# sphericon_v2_lipo_safety.net
KiCad netlist of a schematic drawn in EAGLE
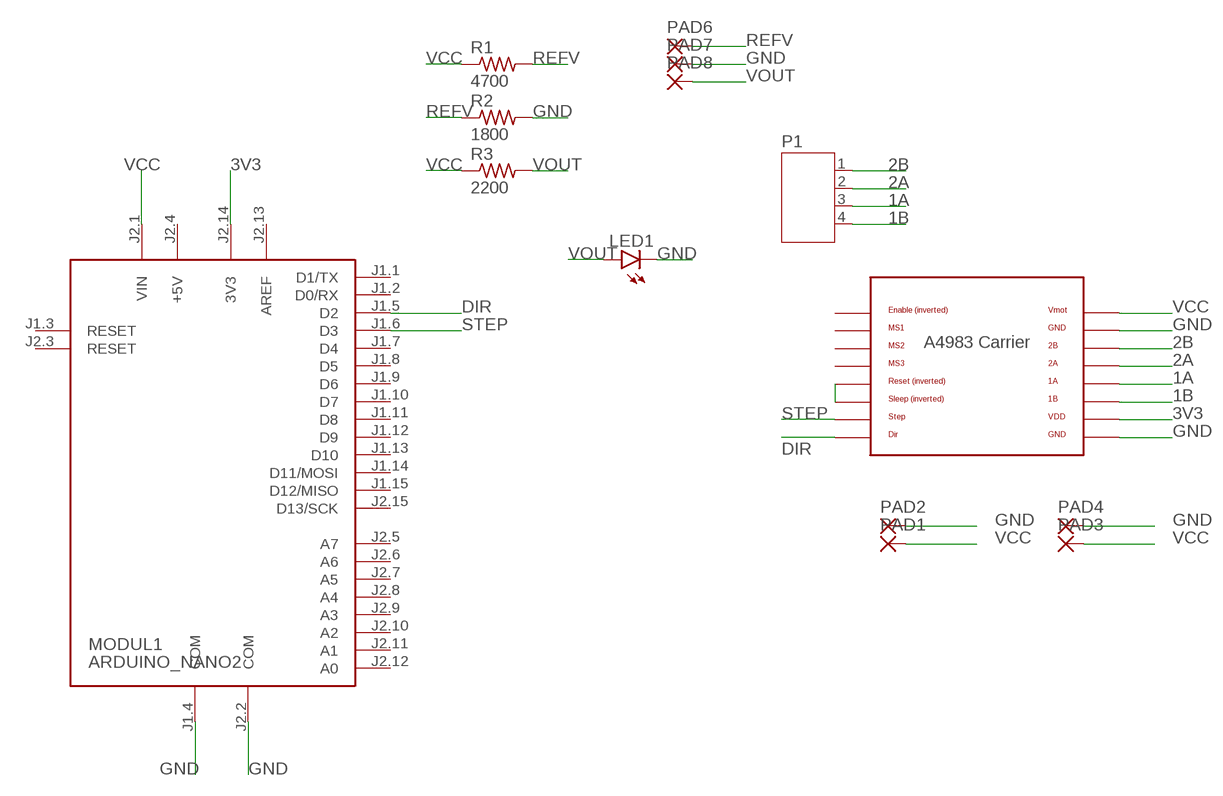
[diagram p0: schematic, sheet 1]

(export (version "E")
  (design (tool "Eeschema 10.0.6"))
  (components
    (comp (ref "LED1")
      (value "LED3MM")
      (footprint "eagle-import:LED3MM")
      (libsource (lib "eagle-import") (part "LED3MM"))
    )
    (comp (ref "MODUL1")
      (value "ARDUINO_NANO2")
      (footprint "eagle-import:ARDUINO_NANO2")
      (libsource (lib "eagle-import") (part "ARDUINO_NANO2"))
    )
    (comp (ref "P1")
      (value "JST-PH4")
      (footprint "eagle-import:JST-PH4")
      (libsource (lib "eagle-import") (part "JST-PH4"))
    )
    (comp (ref "PAD1")
      (value "1,6/0,8")
      (footprint "eagle-import:1,6_0,8")
      (libsource (lib "eagle-import") (part "1,6/0,8"))
    )
    (comp (ref "PAD2")
      (value "1,6/0,8")
      (footprint "eagle-import:1,6_0,8")
      (libsource (lib "eagle-import") (part "1,6/0,8"))
    )
    (comp (ref "PAD3")
      (value "1,6/0,8")
      (footprint "eagle-import:1,6_0,8")
      (libsource (lib "eagle-import") (part "1,6/0,8"))
    )
    (comp (ref "PAD4")
      (value "1,6/0,8")
      (footprint "eagle-import:1,6_0,8")
      (libsource (lib "eagle-import") (part "1,6/0,8"))
    )
    (comp (ref "PAD6")
      (value "1,6/0,8")
      (footprint "eagle-import:1,6_0,8")
      (libsource (lib "eagle-import") (part "1,6/0,8"))
    )
    (comp (ref "PAD7")
      (value "1,6/0,8")
      (footprint "eagle-import:1,6_0,8")
      (libsource (lib "eagle-import") (part "1,6/0,8"))
    )
    (comp (ref "PAD8")
      (value "1,6/0,8")
      (footprint "eagle-import:1,6_0,8")
      (libsource (lib "eagle-import") (part "1,6/0,8"))
    )
    (comp (ref "R1")
      (value "4700")
      (footprint "eagle-import:0204V")
      (libsource (lib "eagle-import") (part "R-US_0204/2V"))
    )
    (comp (ref "R2")
      (value "1800")
      (footprint "eagle-import:0204V")
      (libsource (lib "eagle-import") (part "R-US_0204/2V"))
    )
    (comp (ref "R3")
      (value "2200")
      (footprint "eagle-import:0204V")
      (libsource (lib "eagle-import") (part "R-US_0204/2V"))
    )
    (comp (ref "U$6")
      (value "POLOLU_A4983CARRIER")
      (footprint "eagle-import:A4983CARRIER")
      (libsource (lib "eagle-import") (part "POLOLU_A4983CARRIER"))
    )
  )
  (nets
    (net (code "1") (name "+5V") (class "Default")
      (node (ref "MODUL1") (pin "J2.4") (pinfunction "+5V_J2.4") (pintype "power_in"))
    )
    (net (code "2") (name "1A") (class "Default")
      (node (ref "P1") (pin "3") (pinfunction "3_3") (pintype "passive"))
      (node (ref "U$6") (pin "1A") (pinfunction "1A_1A") (pintype "output"))
    )
    (net (code "3") (name "1B") (class "Default")
      (node (ref "P1") (pin "4") (pinfunction "4_4") (pintype "passive"))
      (node (ref "U$6") (pin "1B") (pinfunction "1B_1B") (pintype "output"))
    )
    (net (code "4") (name "2A") (class "Default")
      (node (ref "P1") (pin "2") (pinfunction "2_2") (pintype "passive"))
      (node (ref "U$6") (pin "2A") (pinfunction "2A_2A") (pintype "output"))
    )
    (net (code "5") (name "2B") (class "Default")
      (node (ref "P1") (pin "1") (pinfunction "1_1") (pintype "passive"))
      (node (ref "U$6") (pin "2B") (pinfunction "2B_2B") (pintype "output"))
    )
    (net (code "6") (name "3V3") (class "Default")
      (node (ref "MODUL1") (pin "J2.14") (pinfunction "3V3_J2.14") (pintype "power_in"))
      (node (ref "U$6") (pin "VDD") (pinfunction "VDD_VDD") (pintype "power_in"))
    )
    (net (code "7") (name "AREF") (class "Default")
      (node (ref "MODUL1") (pin "J2.13") (pinfunction "AREF_J2.13") (pintype "power_in"))
    )
    (net (code "8") (name "DIR") (class "Default")
      (node (ref "MODUL1") (pin "J1.5") (pinfunction "D2_J1.5") (pintype "bidirectional"))
      (node (ref "U$6") (pin "DIR") (pinfunction "DIR_DIR") (pintype "input"))
    )
    (net (code "9") (name "GND") (class "Default")
      (node (ref "LED1") (pin "K") (pinfunction "C_K") (pintype "passive"))
      (node (ref "MODUL1") (pin "J1.4") (pinfunction "COM_J1.4") (pintype "power_in"))
      (node (ref "MODUL1") (pin "J2.2") (pinfunction "COM_J2.2") (pintype "power_in"))
      (node (ref "PAD2") (pin "1") (pinfunction "P_1") (pintype "passive"))
      (node (ref "PAD4") (pin "1") (pinfunction "P_1") (pintype "passive"))
      (node (ref "PAD7") (pin "1") (pinfunction "P_1") (pintype "passive"))
      (node (ref "R2") (pin "2") (pinfunction "2_2") (pintype "passive"))
      (node (ref "U$6") (pin "GND") (pinfunction "GND_GND") (pintype "power_in"))
      (node (ref "U$6") (pin "GND@0") (pinfunction "GND_GND@0") (pintype "power_in"))
    )
    (net (code "10") (name "Net-(U$6-SLEEP)") (class "Default")
      (node (ref "U$6") (pin "RST") (pinfunction "RST_RST") (pintype "input"))
      (node (ref "U$6") (pin "SLP") (pinfunction "SLEEP_SLP") (pintype "input"))
    )
    (net (code "11") (name "REFV") (class "Default")
      (node (ref "PAD6") (pin "1") (pinfunction "P_1") (pintype "passive"))
      (node (ref "R1") (pin "2") (pinfunction "2_2") (pintype "passive"))
      (node (ref "R2") (pin "1") (pinfunction "1_1") (pintype "passive"))
    )
    (net (code "12") (name "STEP") (class "Default")
      (node (ref "MODUL1") (pin "J1.6") (pinfunction "D3_J1.6") (pintype "bidirectional"))
      (node (ref "U$6") (pin "STEP") (pinfunction "STEP_STEP") (pintype "input"))
    )
    (net (code "13") (name "VCC") (class "Default")
      (node (ref "MODUL1") (pin "J2.1") (pinfunction "VIN_J2.1") (pintype "power_in"))
      (node (ref "PAD1") (pin "1") (pinfunction "P_1") (pintype "passive"))
      (node (ref "PAD3") (pin "1") (pinfunction "P_1") (pintype "passive"))
      (node (ref "R1") (pin "1") (pinfunction "1_1") (pintype "passive"))
      (node (ref "R3") (pin "1") (pinfunction "1_1") (pintype "passive"))
      (node (ref "U$6") (pin "VMOT") (pinfunction "VMOT_VMOT") (pintype "power_in"))
    )
    (net (code "14") (name "VOUT") (class "Default")
      (node (ref "LED1") (pin "A") (pinfunction "A_A") (pintype "passive"))
      (node (ref "PAD8") (pin "1") (pinfunction "P_1") (pintype "passive"))
      (node (ref "R3") (pin "2") (pinfunction "2_2") (pintype "passive"))
    )
    (net (code "15") (name "unconnected-(MODUL1-A0-PadJ2.12)") (class "Default")
      (node (ref "MODUL1") (pin "J2.12") (pinfunction "A0_J2.12") (pintype "bidirectional"))
    )
    (net (code "16") (name "unconnected-(MODUL1-A1-PadJ2.11)") (class "Default")
      (node (ref "MODUL1") (pin "J2.11") (pinfunction "A1_J2.11") (pintype "bidirectional"))
    )
    (net (code "17") (name "unconnected-(MODUL1-A2-PadJ2.10)") (class "Default")
      (node (ref "MODUL1") (pin "J2.10") (pinfunction "A2_J2.10") (pintype "bidirectional"))
    )
    (net (code "18") (name "unconnected-(MODUL1-A3-PadJ2.9)") (class "Default")
      (node (ref "MODUL1") (pin "J2.9") (pinfunction "A3_J2.9") (pintype "bidirectional"))
    )
    (net (code "19") (name "unconnected-(MODUL1-A4-PadJ2.8)") (class "Default")
      (node (ref "MODUL1") (pin "J2.8") (pinfunction "A4_J2.8") (pintype "bidirectional"))
    )
    (net (code "20") (name "unconnected-(MODUL1-A5-PadJ2.7)") (class "Default")
      (node (ref "MODUL1") (pin "J2.7") (pinfunction "A5_J2.7") (pintype "bidirectional"))
    )
    (net (code "21") (name "unconnected-(MODUL1-A6-PadJ2.6)") (class "Default")
      (node (ref "MODUL1") (pin "J2.6") (pinfunction "A6_J2.6") (pintype "bidirectional"))
    )
    (net (code "22") (name "unconnected-(MODUL1-A7-PadJ2.5)") (class "Default")
      (node (ref "MODUL1") (pin "J2.5") (pinfunction "A7_J2.5") (pintype "bidirectional"))
    )
    (net (code "23") (name "unconnected-(MODUL1-D0{slash}RX-PadJ1.2)") (class "Default")
      (node (ref "MODUL1") (pin "J1.2") (pinfunction "D0/RX_J1.2") (pintype "bidirectional"))
    )
    (net (code "24") (name "unconnected-(MODUL1-D1{slash}TX-PadJ1.1)") (class "Default")
      (node (ref "MODUL1") (pin "J1.1") (pinfunction "D1/TX_J1.1") (pintype "bidirectional"))
    )
    (net (code "25") (name "unconnected-(MODUL1-D4-PadJ1.7)") (class "Default")
      (node (ref "MODUL1") (pin "J1.7") (pinfunction "D4_J1.7") (pintype "bidirectional"))
    )
    (net (code "26") (name "unconnected-(MODUL1-D5-PadJ1.8)") (class "Default")
      (node (ref "MODUL1") (pin "J1.8") (pinfunction "D5_J1.8") (pintype "bidirectional"))
    )
    (net (code "27") (name "unconnected-(MODUL1-D6-PadJ1.9)") (class "Default")
      (node (ref "MODUL1") (pin "J1.9") (pinfunction "D6_J1.9") (pintype "bidirectional"))
    )
    (net (code "28") (name "unconnected-(MODUL1-D7-PadJ1.10)") (class "Default")
      (node (ref "MODUL1") (pin "J1.10") (pinfunction "D7_J1.10") (pintype "bidirectional"))
    )
    (net (code "29") (name "unconnected-(MODUL1-D8-PadJ1.11)") (class "Default")
      (node (ref "MODUL1") (pin "J1.11") (pinfunction "D8_J1.11") (pintype "bidirectional"))
    )
    (net (code "30") (name "unconnected-(MODUL1-D9-PadJ1.12)") (class "Default")
      (node (ref "MODUL1") (pin "J1.12") (pinfunction "D9_J1.12") (pintype "bidirectional"))
    )
    (net (code "31") (name "unconnected-(MODUL1-D10-PadJ1.13)") (class "Default")
      (node (ref "MODUL1") (pin "J1.13") (pinfunction "D10_J1.13") (pintype "bidirectional"))
    )
    (net (code "32") (name "unconnected-(MODUL1-D11{slash}MOSI-PadJ1.14)") (class "Default")
      (node (ref "MODUL1") (pin "J1.14") (pinfunction "D11/MOSI_J1.14") (pintype "bidirectional"))
    )
    (net (code "33") (name "unconnected-(MODUL1-D12{slash}MISO-PadJ1.15)") (class "Default")
      (node (ref "MODUL1") (pin "J1.15") (pinfunction "D12/MISO_J1.15") (pintype "bidirectional"))
    )
    (net (code "34") (name "unconnected-(MODUL1-D13{slash}SCK-PadJ2.15)") (class "Default")
      (node (ref "MODUL1") (pin "J2.15") (pinfunction "D13/SCK_J2.15") (pintype "bidirectional"))
    )
    (net (code "35") (name "unconnected-(MODUL1-RESET-PadJ1.3)") (class "Default")
      (node (ref "MODUL1") (pin "J1.3") (pinfunction "RESET_J1.3") (pintype "bidirectional"))
    )
    (net (code "36") (name "unconnected-(MODUL1-RESET-PadJ2.3)") (class "Default")
      (node (ref "MODUL1") (pin "J2.3") (pinfunction "RESET_J2.3") (pintype "bidirectional"))
    )
    (net (code "37") (name "unconnected-(U$6-PadEN)") (class "Default")
      (node (ref "U$6") (pin "EN") (pinfunction "EN_EN") (pintype "input"))
    )
    (net (code "38") (name "unconnected-(U$6-PadMS1)") (class "Default")
      (node (ref "U$6") (pin "MS1") (pinfunction "MS1_MS1") (pintype "input"))
    )
    (net (code "39") (name "unconnected-(U$6-PadMS2)") (class "Default")
      (node (ref "U$6") (pin "MS2") (pinfunction "MS2_MS2") (pintype "input"))
    )
    (net (code "40") (name "unconnected-(U$6-PadMS3)") (class "Default")
      (node (ref "U$6") (pin "MS3") (pinfunction "MS3_MS3") (pintype "input"))
    )
  )
)
